# WOW_Scanner.net
KiCad netlist of a schematic drawn in EAGLE
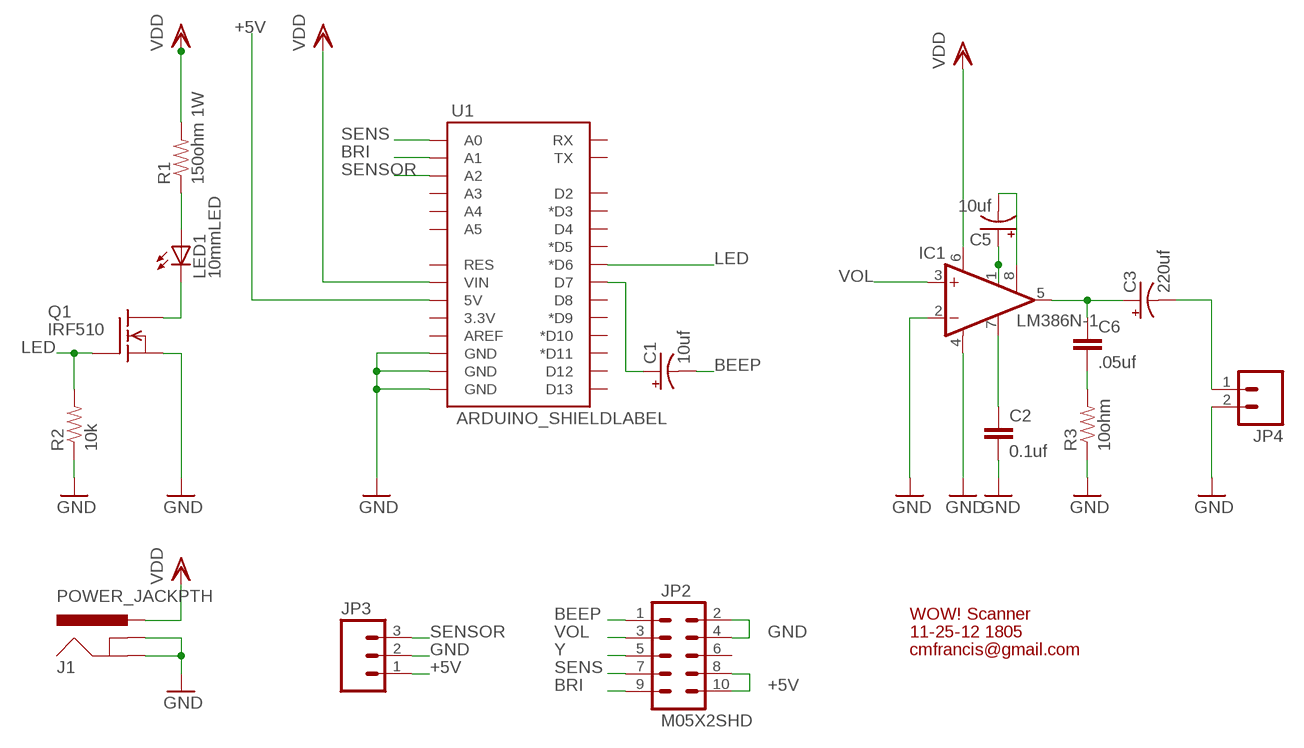
[diagram p0: schematic, sheet 1]

(export (version "E")
  (design (tool "Eeschema 10.0.6"))
  (components
    (comp (ref "C1")
      (value "10uf")
      (footprint "eagle-import:CPOL-RADIAL-10UF-25V")
      (libsource (lib "eagle-import") (part "CAP_POLPTH2"))
    )
    (comp (ref "C2")
      (value "0.1uf")
      (footprint "eagle-import:CAP-PTH-SMALL")
      (libsource (lib "eagle-import") (part "CAPPTH"))
    )
    (comp (ref "C3")
      (value "220uf")
      (footprint "eagle-import:CPOL-RADIAL-100UF-25V")
      (libsource (lib "eagle-import") (part "CAP_POLPTH1"))
    )
    (comp (ref "C5")
      (value "10uf")
      (footprint "eagle-import:CPOL-RADIAL-10UF-25V")
      (libsource (lib "eagle-import") (part "CAP_POLPTH2"))
    )
    (comp (ref "C6")
      (value ".05uf")
      (footprint "eagle-import:CAP-PTH-SMALL")
      (libsource (lib "eagle-import") (part "CAPPTH"))
    )
    (comp (ref "IC1")
      (value "LM386N-1")
      (footprint "eagle-import:DIL08")
      (libsource (lib "eagle-import") (part "LM386?-N1"))
    )
    (comp (ref "J1")
      (value "POWER_JACKPTH")
      (footprint "eagle-import:POWER_JACK_PTH")
      (libsource (lib "eagle-import") (part "POWER_JACKPTH"))
    )
    (comp (ref "JP2")
      (value "M05X2SHD")
      (footprint "eagle-import:2X5-SHROUDED")
      (libsource (lib "eagle-import") (part "M05X2SHD"))
    )
    (comp (ref "JP3")
      (value "M03JST-PTH")
      (footprint "eagle-import:JST-3-PTH")
      (libsource (lib "eagle-import") (part "M03JST-PTH"))
    )
    (comp (ref "JP4")
      (value "M02PTH")
      (footprint "eagle-import:1X02")
      (libsource (lib "eagle-import") (part "M02PTH"))
    )
    (comp (ref "LED1")
      (value "10mmLED")
      (footprint "eagle-import:LED10MM")
      (libsource (lib "eagle-import") (part "LED10MM"))
    )
    (comp (ref "Q1")
      (value "IRF510")
      (footprint "eagle-import:TO220")
      (libsource (lib "eagle-import") (part "IRF510"))
    )
    (comp (ref "R1")
      (value "150ohm 1W")
      (footprint "eagle-import:AXIAL-0.6")
      (libsource (lib "eagle-import") (part "RESISTORPTH-1W"))
    )
    (comp (ref "R2")
      (value "10k")
      (footprint "eagle-import:AXIAL-0.4")
      (libsource (lib "eagle-import") (part "RESISTORPTH-1/4W"))
    )
    (comp (ref "R3")
      (value "10ohm")
      (footprint "eagle-import:AXIAL-0.4")
      (libsource (lib "eagle-import") (part "RESISTORPTH-1/4W"))
    )
    (comp (ref "U1")
      (value "ARDUINO_SHIELDLABEL")
      (footprint "eagle-import:DUEMILANOVE_SHIELD")
      (libsource (lib "eagle-import") (part "ARDUINO_SHIELDLABEL"))
    )
  )
  (nets
    (net (code "1") (name "/+5V") (class "Default")
      (node (ref "JP2") (pin "10") (pinfunction "10_10") (pintype "passive"))
      (node (ref "JP2") (pin "8") (pinfunction "8_8") (pintype "passive"))
      (node (ref "JP3") (pin "1") (pinfunction "1_1") (pintype "passive"))
      (node (ref "U1") (pin "5V") (pinfunction "5V_5V") (pintype "bidirectional"))
    )
    (net (code "2") (name "/BEEP") (class "Default")
      (node (ref "C1") (pin "2") (pinfunction "-_2") (pintype "passive"))
      (node (ref "JP2") (pin "1") (pinfunction "1_1") (pintype "passive"))
    )
    (net (code "3") (name "/BRI") (class "Default")
      (node (ref "JP2") (pin "9") (pinfunction "9_9") (pintype "passive"))
      (node (ref "U1") (pin "A1") (pinfunction "A1_A1") (pintype "bidirectional"))
    )
    (net (code "4") (name "/LED") (class "Default")
      (node (ref "Q1") (pin "1") (pinfunction "G_1") (pintype "passive"))
      (node (ref "R2") (pin "P$2") (pinfunction "2_P$2") (pintype "passive"))
      (node (ref "U1") (pin "D6") (pinfunction "*D6_D6") (pintype "bidirectional"))
    )
    (net (code "5") (name "/SENS") (class "Default")
      (node (ref "JP2") (pin "7") (pinfunction "7_7") (pintype "passive"))
      (node (ref "U1") (pin "A0") (pinfunction "A0_A0") (pintype "bidirectional"))
    )
    (net (code "6") (name "/SENSOR") (class "Default")
      (node (ref "JP3") (pin "3") (pinfunction "3_3") (pintype "passive"))
      (node (ref "U1") (pin "A2") (pinfunction "A2_A2") (pintype "bidirectional"))
    )
    (net (code "7") (name "/VOL") (class "Default")
      (node (ref "IC1") (pin "3") (pinfunction "+IN_3") (pintype "input"))
      (node (ref "JP2") (pin "3") (pinfunction "3_3") (pintype "passive"))
    )
    (net (code "8") (name "/Y") (class "Default")
      (node (ref "JP2") (pin "5") (pinfunction "5_5") (pintype "passive"))
    )
    (net (code "9") (name "GND") (class "Default")
      (node (ref "C2") (pin "2") (pinfunction "2_2") (pintype "passive"))
      (node (ref "IC1") (pin "2") (pinfunction "-IN_2") (pintype "input"))
      (node (ref "IC1") (pin "4") (pinfunction "GND_4") (pintype "power_in"))
      (node (ref "J1") (pin "GND") (pinfunction "GND_GND") (pintype "bidirectional"))
      (node (ref "J1") (pin "GNDBREAK") (pinfunction "GNDBREAK_GNDBREAK") (pintype "bidirectional"))
      (node (ref "JP2") (pin "2") (pinfunction "2_2") (pintype "passive"))
      (node (ref "JP2") (pin "4") (pinfunction "4_4") (pintype "passive"))
      (node (ref "JP3") (pin "2") (pinfunction "2_2") (pintype "passive"))
      (node (ref "JP4") (pin "2") (pinfunction "2_2") (pintype "passive"))
      (node (ref "Q1") (pin "3") (pinfunction "S_3") (pintype "passive"))
      (node (ref "R2") (pin "P$1") (pinfunction "1_P$1") (pintype "passive"))
      (node (ref "R3") (pin "P$1") (pinfunction "1_P$1") (pintype "passive"))
      (node (ref "U1") (pin "GND@0") (pinfunction "GND_GND@0") (pintype "bidirectional"))
      (node (ref "U1") (pin "GND@1") (pinfunction "GND_GND@1") (pintype "bidirectional"))
      (node (ref "U1") (pin "GND@2") (pinfunction "GND_GND@2") (pintype "bidirectional"))
    )
    (net (code "10") (name "Net-(C1-+)") (class "Default")
      (node (ref "C1") (pin "1") (pinfunction "+_1") (pintype "passive"))
      (node (ref "U1") (pin "D7") (pinfunction "D7_D7") (pintype "bidirectional"))
    )
    (net (code "11") (name "Net-(C3-+)") (class "Default")
      (node (ref "C3") (pin "1") (pinfunction "+_1") (pintype "passive"))
      (node (ref "C6") (pin "1") (pinfunction "1_1") (pintype "passive"))
      (node (ref "IC1") (pin "5") (pinfunction "OUT_5") (pintype "output"))
    )
    (net (code "12") (name "Net-(C3--)") (class "Default")
      (node (ref "C3") (pin "2") (pinfunction "-_2") (pintype "passive"))
      (node (ref "JP4") (pin "1") (pinfunction "1_1") (pintype "passive"))
    )
    (net (code "13") (name "Net-(C5-+)") (class "Default")
      (node (ref "C5") (pin "1") (pinfunction "+_1") (pintype "passive"))
      (node (ref "IC1") (pin "1") (pinfunction "GAIN_1") (pintype "passive"))
    )
    (net (code "14") (name "Net-(C5--)") (class "Default")
      (node (ref "C5") (pin "2") (pinfunction "-_2") (pintype "passive"))
      (node (ref "IC1") (pin "8") (pinfunction "GAIN_8") (pintype "passive"))
    )
    (net (code "15") (name "Net-(IC1-BYPASS)") (class "Default")
      (node (ref "C2") (pin "1") (pinfunction "1_1") (pintype "passive"))
      (node (ref "IC1") (pin "7") (pinfunction "BYPASS_7") (pintype "passive"))
    )
    (net (code "16") (name "Net-(Q1-D)") (class "Default")
      (node (ref "LED1") (pin "C") (pinfunction "C_C") (pintype "passive"))
      (node (ref "Q1") (pin "2") (pinfunction "D_2") (pintype "passive"))
    )
    (net (code "17") (name "Net-(R1-1)") (class "Default")
      (node (ref "LED1") (pin "A") (pinfunction "A_A") (pintype "passive"))
      (node (ref "R1") (pin "P$1") (pinfunction "1_P$1") (pintype "passive"))
    )
    (net (code "18") (name "Net-(R3-2)") (class "Default")
      (node (ref "C6") (pin "2") (pinfunction "2_2") (pintype "passive"))
      (node (ref "R3") (pin "P$2") (pinfunction "2_P$2") (pintype "passive"))
    )
    (net (code "19") (name "VDD") (class "Default")
      (node (ref "IC1") (pin "6") (pinfunction "VS_6") (pintype "power_in"))
      (node (ref "J1") (pin "PWR") (pinfunction "PWR_PWR") (pintype "bidirectional"))
      (node (ref "R1") (pin "P$2") (pinfunction "2_P$2") (pintype "passive"))
      (node (ref "U1") (pin "VIN") (pinfunction "VIN_VIN") (pintype "bidirectional"))
    )
    (net (code "20") (name "unconnected-(JP2-Pad6)") (class "Default")
      (node (ref "JP2") (pin "6") (pinfunction "6_6") (pintype "passive"))
    )
    (net (code "21") (name "unconnected-(U1-*D3-PadD3)") (class "Default")
      (node (ref "U1") (pin "D3") (pinfunction "*D3_D3") (pintype "bidirectional"))
    )
    (net (code "22") (name "unconnected-(U1-*D5-PadD5)") (class "Default")
      (node (ref "U1") (pin "D5") (pinfunction "*D5_D5") (pintype "bidirectional"))
    )
    (net (code "23") (name "unconnected-(U1-*D9-PadD9)") (class "Default")
      (node (ref "U1") (pin "D9") (pinfunction "*D9_D9") (pintype "bidirectional"))
    )
    (net (code "24") (name "unconnected-(U1-*D10-PadD10)") (class "Default")
      (node (ref "U1") (pin "D10") (pinfunction "*D10_D10") (pintype "bidirectional"))
    )
    (net (code "25") (name "unconnected-(U1-*D11-PadD11)") (class "Default")
      (node (ref "U1") (pin "D11") (pinfunction "*D11_D11") (pintype "bidirectional"))
    )
    (net (code "26") (name "unconnected-(U1-Pad3.3V)") (class "Default")
      (node (ref "U1") (pin "3.3V") (pinfunction "3.3V_3.3V") (pintype "bidirectional"))
    )
    (net (code "27") (name "unconnected-(U1-PadA3)") (class "Default")
      (node (ref "U1") (pin "A3") (pinfunction "A3_A3") (pintype "bidirectional"))
    )
    (net (code "28") (name "unconnected-(U1-PadA4)") (class "Default")
      (node (ref "U1") (pin "A4") (pinfunction "A4_A4") (pintype "bidirectional"))
    )
    (net (code "29") (name "unconnected-(U1-PadA5)") (class "Default")
      (node (ref "U1") (pin "A5") (pinfunction "A5_A5") (pintype "bidirectional"))
    )
    (net (code "30") (name "unconnected-(U1-PadAREF)") (class "Default")
      (node (ref "U1") (pin "AREF") (pinfunction "AREF_AREF") (pintype "bidirectional"))
    )
    (net (code "31") (name "unconnected-(U1-PadD2)") (class "Default")
      (node (ref "U1") (pin "D2") (pinfunction "D2_D2") (pintype "bidirectional"))
    )
    (net (code "32") (name "unconnected-(U1-PadD4)") (class "Default")
      (node (ref "U1") (pin "D4") (pinfunction "D4_D4") (pintype "bidirectional"))
    )
    (net (code "33") (name "unconnected-(U1-PadD8)") (class "Default")
      (node (ref "U1") (pin "D8") (pinfunction "D8_D8") (pintype "bidirectional"))
    )
    (net (code "34") (name "unconnected-(U1-PadD12)") (class "Default")
      (node (ref "U1") (pin "D12") (pinfunction "D12_D12") (pintype "bidirectional"))
    )
    (net (code "35") (name "unconnected-(U1-PadD13)") (class "Default")
      (node (ref "U1") (pin "D13") (pinfunction "D13_D13") (pintype "bidirectional"))
    )
    (net (code "36") (name "unconnected-(U1-PadRES)") (class "Default")
      (node (ref "U1") (pin "RES") (pinfunction "RES_RES") (pintype "bidirectional"))
    )
    (net (code "37") (name "unconnected-(U1-PadRX)") (class "Default")
      (node (ref "U1") (pin "RX") (pinfunction "RX_RX") (pintype "bidirectional"))
    )
    (net (code "38") (name "unconnected-(U1-PadTX)") (class "Default")
      (node (ref "U1") (pin "TX") (pinfunction "TX_TX") (pintype "bidirectional"))
    )
  )
)
